# PowerSupply.net
KiCad netlist of a schematic drawn in EAGLE
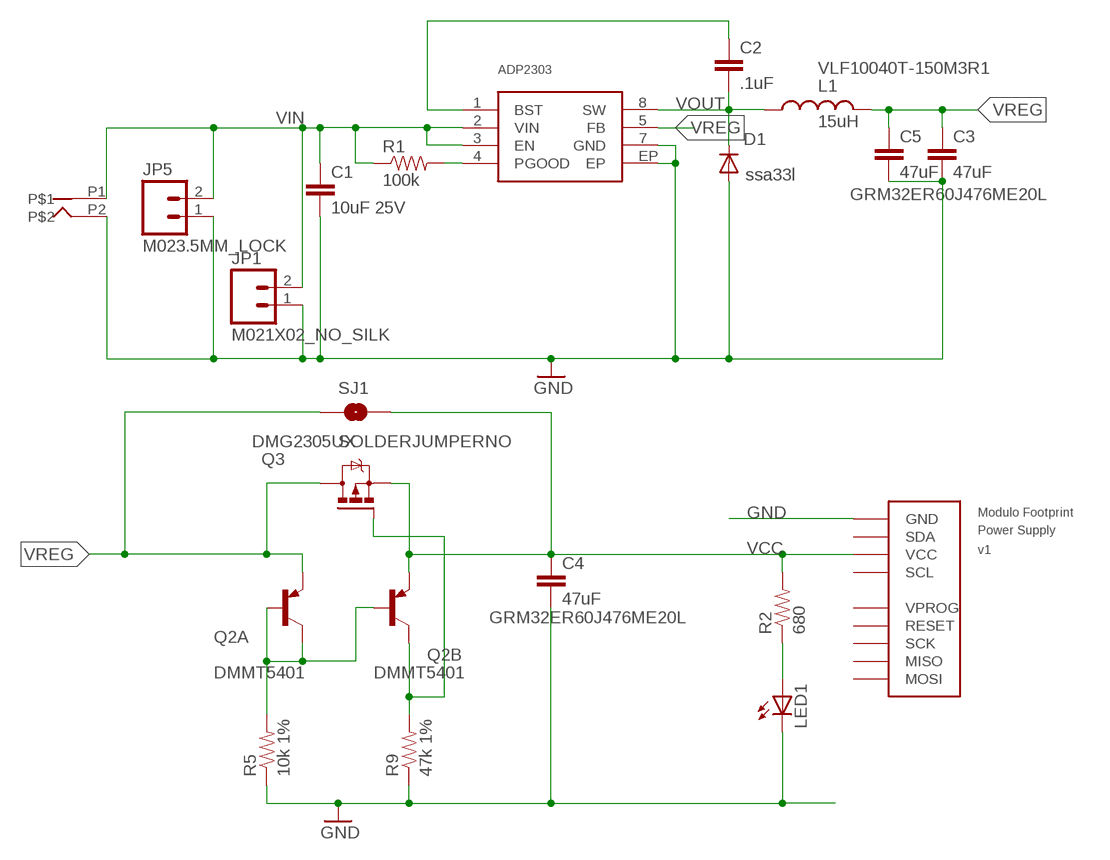
[diagram p0: schematic, sheet 1]

(export (version "E")
  (design (tool "Eeschema 10.0.6"))
  (components
    (comp (ref "C1")
      (value "10uF 25V")
      (footprint "eagle-import:0805")
      (libsource (lib "eagle-import") (part "CAP0805"))
    )
    (comp (ref "C2")
      (value ".1uF")
      (footprint "eagle-import:0805")
      (libsource (lib "eagle-import") (part "CAP0805"))
    )
    (comp (ref "C3")
      (value "47uF")
      (footprint "eagle-import:1210")
      (libsource (lib "eagle-import") (part "CAP1210"))
    )
    (comp (ref "C4")
      (value "47uF")
      (footprint "eagle-import:1210")
      (libsource (lib "eagle-import") (part "CAP1210"))
    )
    (comp (ref "C5")
      (value "47uF")
      (footprint "eagle-import:1210")
      (libsource (lib "eagle-import") (part "CAP1210"))
    )
    (comp (ref "D1")
      (value "ssa33l")
      (footprint "eagle-import:SMA-DIODE")
      (libsource (lib "eagle-import") (part "DIODESMA"))
    )
    (comp (ref "JP1")
      (value "M021X02_NO_SILK")
      (footprint "eagle-import:1X02_NO_SILK")
      (libsource (lib "eagle-import") (part "M021X02_NO_SILK"))
    )
    (comp (ref "JP5")
      (value "M023.5MM_LOCK")
      (footprint "eagle-import:SCREWTERMINAL-3.5MM-2_LOCK")
      (libsource (lib "eagle-import") (part "M023.5MM_LOCK"))
    )
    (comp (ref "L1")
      (value "15uH")
      (footprint "eagle-import:INDUCTOR-VLF10040")
      (libsource (lib "eagle-import") (part "INDUCTORVLF10040"))
    )
    (comp (ref "LED1")
      (value "LEDCHIPLED_0805")
      (footprint "eagle-import:CHIPLED_0805")
      (libsource (lib "eagle-import") (part "LEDCHIPLED_0805"))
    )
    (comp (ref "Q2")
      (value "DMMT5401")
      (footprint "eagle-import:SOT-26")
      (libsource (lib "eagle-import") (part "TRANSISTOR-DUAL-PNP"))
    )
    (comp (ref "Q3")
      (value "DMG2305UX")
      (footprint "eagle-import:MICRO3")
      (libsource (lib "eagle-import") (part "IRLML5203"))
    )
    (comp (ref "R1")
      (value "100k")
      (footprint "eagle-import:0805")
      (libsource (lib "eagle-import") (part "SparkFun-Resistors_RESISTOR0805-RES"))
    )
    (comp (ref "R2")
      (value "680")
      (footprint "eagle-import:0805")
      (libsource (lib "eagle-import") (part "RESISTOR0805-RES"))
    )
    (comp (ref "R5")
      (value "10k 1%")
      (footprint "eagle-import:0805")
      (libsource (lib "eagle-import") (part "RESISTOR0805-RES"))
    )
    (comp (ref "R9")
      (value "47k 1%")
      (footprint "eagle-import:0805")
      (libsource (lib "eagle-import") (part "RESISTOR0805-RES"))
    )
    (comp (ref "SJ1")
      (value "SOLDERJUMPERNO")
      (footprint "eagle-import:SJ_2S-NO")
      (libsource (lib "eagle-import") (part "SOLDERJUMPERNO"))
    )
    (comp (ref "U$3")
      (value "ADP2303")
      (footprint "eagle-import:SOIC8-EP")
      (libsource (lib "eagle-import") (part "ADP2303"))
    )
    (comp (ref "U$4")
      (value "FOOTPRINTFOOTPRINT-2")
      (footprint "eagle-import:FOOTPRINT2")
      (fields (field (name "BOARD") "Power Supply") (field (name "VERSION") "v1"))
      (libsource (lib "eagle-import") (part "FOOTPRINTFOOTPRINT-2"))
    )
    (comp (ref "U$21")
      (value "DC-JACK")
      (footprint "eagle-import:DC-POWER-JACK")
      (libsource (lib "eagle-import") (part "DC-JACK"))
    )
  )
  (nets
    (net (code "1") (name "/VCC") (class "Default")
      (node (ref "C4") (pin "1") (pinfunction "1_1") (pintype "passive"))
      (node (ref "Q2") (pin "5") (pinfunction "E_5") (pintype "passive"))
      (node (ref "Q3") (pin "2") (pinfunction "S_2") (pintype "passive"))
      (node (ref "R2") (pin "2") (pinfunction "2_2") (pintype "passive"))
      (node (ref "SJ1") (pin "2") (pinfunction "2_2") (pintype "passive"))
      (node (ref "U$4") (pin "BUS2") (pinfunction "VCC_BUS2") (pintype "bidirectional"))
    )
    (net (code "2") (name "/VIN") (class "Default")
      (node (ref "C1") (pin "1") (pinfunction "1_1") (pintype "passive"))
      (node (ref "JP1") (pin "2") (pinfunction "2_2") (pintype "passive"))
      (node (ref "JP5") (pin "2") (pinfunction "2_2") (pintype "passive"))
      (node (ref "R1") (pin "1") (pinfunction "1_1") (pintype "passive"))
      (node (ref "U$21") (pin "P1") (pinfunction "P$1_P1") (pintype "bidirectional"))
      (node (ref "U$3") (pin "2") (pinfunction "VIN_2") (pintype "bidirectional"))
      (node (ref "U$3") (pin "3") (pinfunction "EN_3") (pintype "bidirectional"))
    )
    (net (code "3") (name "/VOUT") (class "Default")
      (node (ref "C2") (pin "2") (pinfunction "2_2") (pintype "passive"))
      (node (ref "D1") (pin "C") (pinfunction "C_C") (pintype "passive"))
      (node (ref "L1") (pin "P$1") (pinfunction "1_P$1") (pintype "passive"))
      (node (ref "U$3") (pin "8") (pinfunction "SW_8") (pintype "bidirectional"))
    )
    (net (code "4") (name "GND") (class "Default")
      (node (ref "C1") (pin "2") (pinfunction "2_2") (pintype "passive"))
      (node (ref "C3") (pin "2") (pinfunction "2_2") (pintype "passive"))
      (node (ref "C4") (pin "2") (pinfunction "2_2") (pintype "passive"))
      (node (ref "C5") (pin "2") (pinfunction "2_2") (pintype "passive"))
      (node (ref "D1") (pin "A") (pinfunction "A_A") (pintype "passive"))
      (node (ref "JP1") (pin "1") (pinfunction "1_1") (pintype "passive"))
      (node (ref "JP5") (pin "1") (pinfunction "1_1") (pintype "passive"))
      (node (ref "LED1") (pin "C") (pinfunction "C_C") (pintype "passive"))
      (node (ref "R5") (pin "1") (pinfunction "1_1") (pintype "passive"))
      (node (ref "R9") (pin "1") (pinfunction "1_1") (pintype "passive"))
      (node (ref "U$21") (pin "P2") (pinfunction "P$2_P2") (pintype "bidirectional"))
      (node (ref "U$3") (pin "7") (pinfunction "GND_7") (pintype "bidirectional"))
      (node (ref "U$3") (pin "EP") (pinfunction "EP_EP") (pintype "bidirectional"))
      (node (ref "U$4") (pin "BUS0") (pinfunction "GND_BUS0") (pintype "bidirectional"))
    )
    (net (code "5") (name "Net-(LED1-PadA)") (class "Default")
      (node (ref "LED1") (pin "A") (pinfunction "A_A") (pintype "passive"))
      (node (ref "R2") (pin "1") (pinfunction "1_1") (pintype "passive"))
    )
    (net (code "6") (name "Net-(Q2A-B)") (class "Default")
      (node (ref "Q2") (pin "1") (pinfunction "C_1") (pintype "passive"))
      (node (ref "Q2") (pin "2") (pinfunction "B_2") (pintype "passive"))
      (node (ref "Q2") (pin "3") (pinfunction "B_3") (pintype "passive"))
      (node (ref "R5") (pin "2") (pinfunction "2_2") (pintype "passive"))
    )
    (net (code "7") (name "Net-(Q2B-C)") (class "Default")
      (node (ref "Q2") (pin "4") (pinfunction "C_4") (pintype "passive"))
      (node (ref "Q3") (pin "1") (pinfunction "G_1") (pintype "passive"))
      (node (ref "R9") (pin "2") (pinfunction "2_2") (pintype "passive"))
    )
    (net (code "8") (name "Net-(U$3-BST)") (class "Default")
      (node (ref "C2") (pin "1") (pinfunction "1_1") (pintype "passive"))
      (node (ref "U$3") (pin "1") (pinfunction "BST_1") (pintype "bidirectional"))
    )
    (net (code "9") (name "Net-(U$3-PGOOD)") (class "Default")
      (node (ref "R1") (pin "2") (pinfunction "2_2") (pintype "passive"))
      (node (ref "U$3") (pin "4") (pinfunction "PGOOD_4") (pintype "bidirectional"))
    )
    (net (code "10") (name "VREG") (class "Default")
      (node (ref "C3") (pin "1") (pinfunction "1_1") (pintype "passive"))
      (node (ref "C5") (pin "1") (pinfunction "1_1") (pintype "passive"))
      (node (ref "L1") (pin "P$2") (pinfunction "2_P$2") (pintype "passive"))
      (node (ref "Q2") (pin "6") (pinfunction "E_6") (pintype "passive"))
      (node (ref "Q3") (pin "3") (pinfunction "D_3") (pintype "passive"))
      (node (ref "SJ1") (pin "1") (pinfunction "1_1") (pintype "passive"))
      (node (ref "U$3") (pin "5") (pinfunction "FB_5") (pintype "bidirectional"))
    )
    (net (code "11") (name "unconnected-(U$4-MISO-PadPROG3)") (class "Default")
      (node (ref "U$4") (pin "PROG3") (pinfunction "MISO_PROG3") (pintype "bidirectional"))
    )
    (net (code "12") (name "unconnected-(U$4-MOSI-PadPROG4)") (class "Default")
      (node (ref "U$4") (pin "PROG4") (pinfunction "MOSI_PROG4") (pintype "bidirectional"))
    )
    (net (code "13") (name "unconnected-(U$4-RESET-PadPROG1)") (class "Default")
      (node (ref "U$4") (pin "PROG1") (pinfunction "RESET_PROG1") (pintype "bidirectional"))
    )
    (net (code "14") (name "unconnected-(U$4-SCK-PadPROG2)") (class "Default")
      (node (ref "U$4") (pin "PROG2") (pinfunction "SCK_PROG2") (pintype "bidirectional"))
    )
    (net (code "15") (name "unconnected-(U$4-SCL-PadBUS3)") (class "Default")
      (node (ref "U$4") (pin "BUS3") (pinfunction "SCL_BUS3") (pintype "bidirectional"))
    )
    (net (code "16") (name "unconnected-(U$4-SDA-PadBUS1)") (class "Default")
      (node (ref "U$4") (pin "BUS1") (pinfunction "SDA_BUS1") (pintype "bidirectional"))
    )
    (net (code "17") (name "unconnected-(U$4-VPROG-PadPROG0)") (class "Default")
      (node (ref "U$4") (pin "PROG0") (pinfunction "VPROG_PROG0") (pintype "bidirectional"))
    )
  )
)
